# Main.net
KiCad netlist of a schematic drawn in Altium Designer
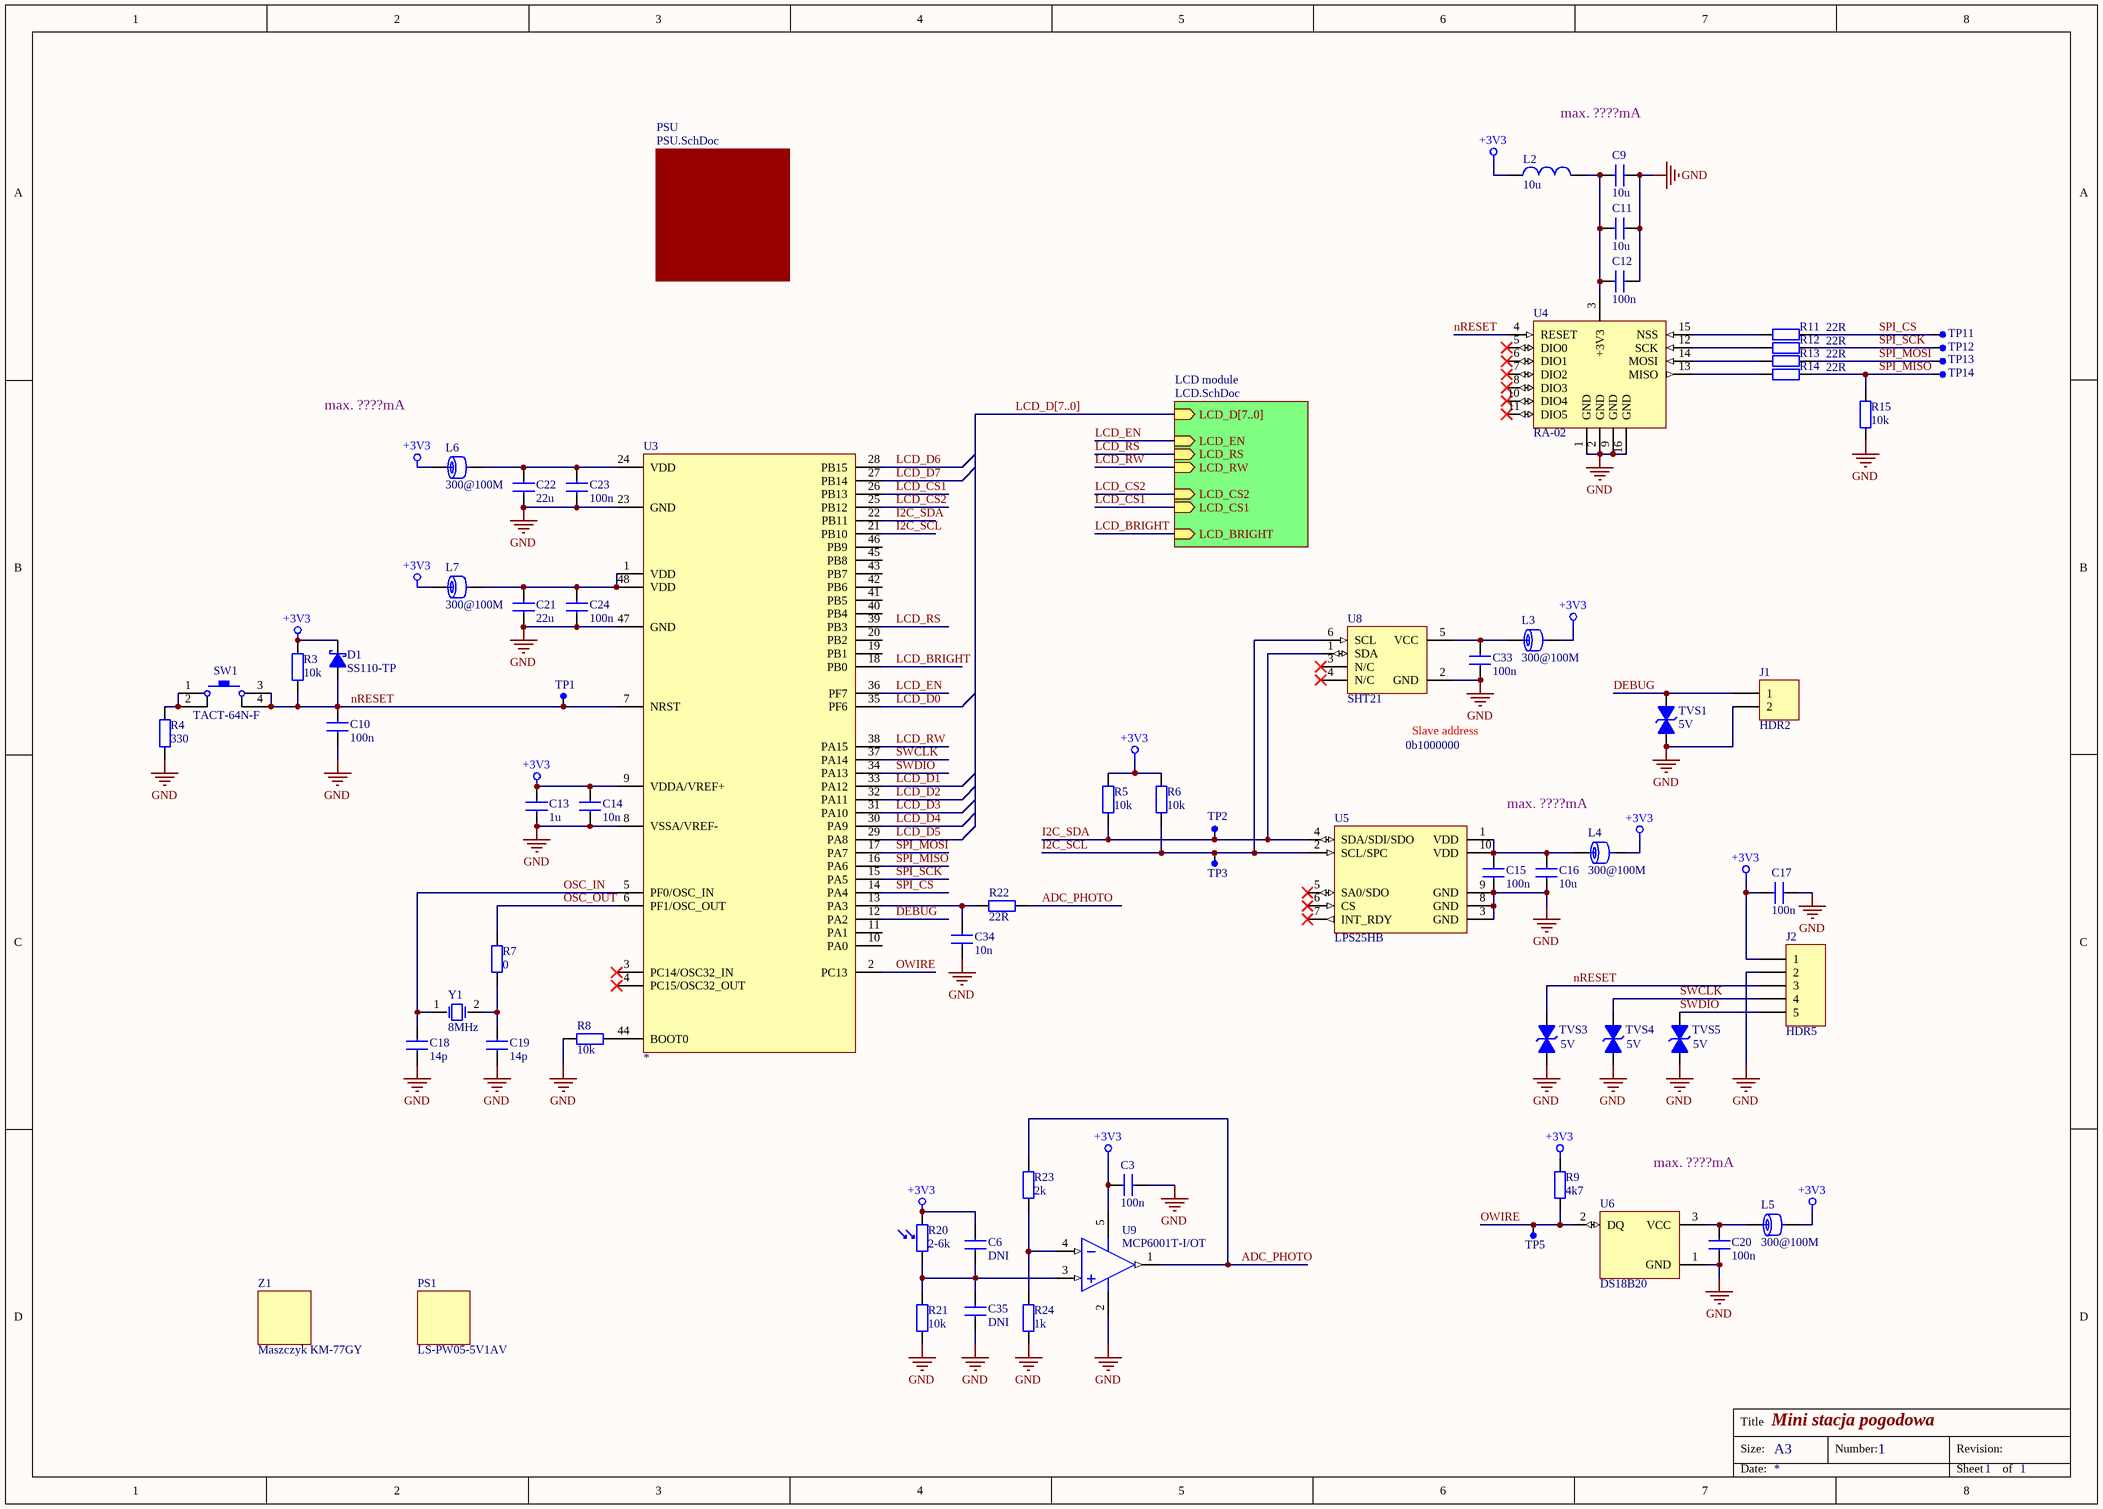
[diagram p0: Main.SchDoc]

(export (version "E")
  (design (tool "Eeschema 10.0.6"))
  (components
    (comp (ref "C3")
      (value "100n")
      (footprint "C_0805")
      (description "Capacitor")
      (libsource (lib "passive") (part "Capacitor"))
    )
    (comp (ref "C6")
      (value "DNI")
      (footprint "C_0805")
      (description "Capacitor")
      (libsource (lib "passive") (part "Capacitor"))
    )
    (comp (ref "C9")
      (value "10u")
      (footprint "C_0805")
      (description "Capacitor")
      (libsource (lib "passive") (part "Capacitor"))
    )
    (comp (ref "C10")
      (value "100n")
      (footprint "C_0805")
      (description "Capacitor")
      (libsource (lib "passive") (part "Capacitor"))
    )
    (comp (ref "C11")
      (value "10u")
      (footprint "C_0805")
      (description "Capacitor")
      (libsource (lib "passive") (part "Capacitor"))
    )
    (comp (ref "C12")
      (value "100n")
      (footprint "C_0805")
      (description "Capacitor")
      (libsource (lib "passive") (part "Capacitor"))
    )
    (comp (ref "C13")
      (value "1u")
      (footprint "C_0805")
      (description "Capacitor")
      (libsource (lib "passive") (part "Capacitor"))
    )
    (comp (ref "C14")
      (value "10n")
      (footprint "C_0805")
      (description "Capacitor")
      (libsource (lib "passive") (part "Capacitor"))
    )
    (comp (ref "C15")
      (value "100n")
      (footprint "C_0805")
      (description "Capacitor")
      (libsource (lib "passive") (part "Capacitor"))
    )
    (comp (ref "C16")
      (value "10u")
      (footprint "C_0805")
      (description "Capacitor")
      (libsource (lib "passive") (part "Capacitor"))
    )
    (comp (ref "C17")
      (value "100n")
      (footprint "C_0805")
      (description "Capacitor")
      (libsource (lib "passive") (part "Capacitor"))
    )
    (comp (ref "C18")
      (value "14p")
      (footprint "C_0805")
      (description "Capacitor")
      (libsource (lib "passive") (part "Capacitor"))
    )
    (comp (ref "C19")
      (value "14p")
      (footprint "C_0805")
      (description "Capacitor")
      (libsource (lib "passive") (part "Capacitor"))
    )
    (comp (ref "C20")
      (value "100n")
      (footprint "C_0805")
      (description "Capacitor")
      (libsource (lib "passive") (part "Capacitor"))
    )
    (comp (ref "C21")
      (value "22u")
      (footprint "C_0805")
      (description "Capacitor")
      (libsource (lib "passive") (part "Capacitor"))
    )
    (comp (ref "C22")
      (value "22u")
      (footprint "C_0805")
      (description "Capacitor")
      (libsource (lib "passive") (part "Capacitor"))
    )
    (comp (ref "C23")
      (value "100n")
      (footprint "C_0805")
      (description "Capacitor")
      (libsource (lib "passive") (part "Capacitor"))
    )
    (comp (ref "C24")
      (value "100n")
      (footprint "C_0805")
      (description "Capacitor")
      (libsource (lib "passive") (part "Capacitor"))
    )
    (comp (ref "C33")
      (value "100n")
      (footprint "C_0805")
      (description "Capacitor")
      (libsource (lib "passive") (part "Capacitor"))
    )
    (comp (ref "C34")
      (value "10n")
      (footprint "C_0805")
      (description "Capacitor")
      (libsource (lib "passive") (part "Capacitor"))
    )
    (comp (ref "C35")
      (value "DNI")
      (footprint "C_0805")
      (description "Capacitor")
      (libsource (lib "passive") (part "Capacitor"))
    )
    (comp (ref "D1")
      (value "SS110-TP")
      (footprint "D_1206")
      (description "Schottky Diode")
      (libsource (lib "passive") (part "Diode Schottky"))
    )
    (comp (ref "J1")
      (value "HDR2")
      (footprint "header 2.54mm 2pin")
      (description "Header, 2-Pin")
      (fields (field (name "Comment") "Header 2"))
      (libsource (lib "mechanical") (part "Header 2"))
    )
    (comp (ref "J2")
      (value "HDR5")
      (footprint "header 2.54mm 5pin")
      (description "Header, 5-Pin")
      (fields (field (name "Comment") "Header 5"))
      (libsource (lib "mechanical") (part "Header 5"))
    )
    (comp (ref "L2")
      (value "10u")
      (footprint "L_0805")
      (description "Inductor")
      (libsource (lib "passive") (part "Inductor"))
    )
    (comp (ref "L3")
      (value "300@100M")
      (footprint "L_0805")
      (description "Ferrite Bead")
      (fields (field (name "Comment") "742792031"))
      (libsource (lib "passive") (part "FB"))
    )
    (comp (ref "L4")
      (value "300@100M")
      (footprint "L_0805")
      (description "Ferrite Bead")
      (fields (field (name "Comment") "742792031"))
      (libsource (lib "passive") (part "FB"))
    )
    (comp (ref "L5")
      (value "300@100M")
      (footprint "L_0805")
      (description "Ferrite Bead")
      (fields (field (name "Comment") "742792031"))
      (libsource (lib "passive") (part "FB"))
    )
    (comp (ref "L6")
      (value "300@100M")
      (footprint "L_0805")
      (description "Ferrite Bead")
      (fields (field (name "Comment") "742792031"))
      (libsource (lib "passive") (part "FB"))
    )
    (comp (ref "L7")
      (value "300@100M")
      (footprint "L_0805")
      (description "Ferrite Bead")
      (fields (field (name "Comment") "742792031"))
      (libsource (lib "passive") (part "FB"))
    )
    (comp (ref "PS1")
      (value "LS-PW05-5V1AV")
      (description "5VDC; 1A; EU; 82,7%")
      (libsource (lib "mechanical") (part "LS-PW05-5V1AV"))
    )
    (comp (ref "R3")
      (value "10k")
      (footprint "R_0805")
      (description "Resistor")
      (libsource (lib "passive") (part "Resistor"))
    )
    (comp (ref "R4")
      (value "330")
      (footprint "R_0805")
      (description "Resistor")
      (libsource (lib "passive") (part "Resistor"))
    )
    (comp (ref "R5")
      (value "10k")
      (footprint "R_1206")
      (description "Resistor")
      (libsource (lib "passive") (part "Resistor"))
    )
    (comp (ref "R6")
      (value "10k")
      (footprint "R_1206")
      (description "Resistor")
      (libsource (lib "passive") (part "Resistor"))
    )
    (comp (ref "R7")
      (value "0")
      (footprint "R_0805")
      (description "Resistor")
      (libsource (lib "passive") (part "Resistor"))
    )
    (comp (ref "R8")
      (value "10k")
      (footprint "R_1206")
      (description "Resistor")
      (libsource (lib "") (part "Resistor_1"))
    )
    (comp (ref "R9")
      (value "4k7")
      (footprint "R_1206")
      (description "Resistor")
      (libsource (lib "boxer_pas") (part "Resistor"))
    )
    (comp (ref "R11")
      (value "22R")
      (footprint "R_0805")
      (description "Resistor")
      (libsource (lib "") (part "Resistor_1"))
    )
    (comp (ref "R12")
      (value "22R")
      (footprint "R_0805")
      (description "Resistor")
      (libsource (lib "") (part "Resistor_1"))
    )
    (comp (ref "R13")
      (value "22R")
      (footprint "R_0805")
      (description "Resistor")
      (libsource (lib "") (part "Resistor_1"))
    )
    (comp (ref "R14")
      (value "22R")
      (footprint "R_0805")
      (description "Resistor")
      (libsource (lib "") (part "Resistor_1"))
    )
    (comp (ref "R15")
      (value "10k")
      (footprint "R_1206")
      (description "Resistor")
      (libsource (lib "passive") (part "Resistor"))
    )
    (comp (ref "R20")
      (value "2-6k")
      (footprint "Photoresistor")
      (description "Photo Resistor")
      (fields (field (name "Comment") "PGM5506-MP"))
      (libsource (lib "passive") (part "Resistor Photo"))
    )
    (comp (ref "R21")
      (value "10k")
      (footprint "R_1206")
      (description "Resistor")
      (libsource (lib "passive") (part "Resistor"))
    )
    (comp (ref "R22")
      (value "22R")
      (footprint "R_0805")
      (description "Resistor")
      (libsource (lib "") (part "Resistor_1"))
    )
    (comp (ref "R23")
      (value "2k")
      (footprint "R_1206")
      (description "Resistor")
      (libsource (lib "passive") (part "Resistor"))
    )
    (comp (ref "R24")
      (value "1k")
      (footprint "R_1206")
      (description "Resistor")
      (libsource (lib "passive") (part "Resistor"))
    )
    (comp (ref "SW1")
      (value "TACT-64N-F")
      (footprint "SPST_NO_1301")
      (description "Switch 4 Pins")
      (fields (field (name "Comment") "Switch-PB 4 Pins"))
      (libsource (lib "mechanical") (part "Switch-PB 4 Pins"))
    )
    (comp (ref "TP1")
      (value "TEST PAD")
      (footprint "PIN")
      (description "PAD 1.5mm")
      (libsource (lib "boxer_mechanical") (part "TEST_PAD"))
    )
    (comp (ref "TP2")
      (value "TEST PAD")
      (footprint "PIN")
      (libsource (lib "boxer_mechanical") (part "TEST_PAD"))
    )
    (comp (ref "TP3")
      (value "TEST PAD")
      (footprint "PIN")
      (libsource (lib "boxer_mechanical") (part "TEST_PAD"))
    )
    (comp (ref "TP5")
      (value "TEST PAD")
      (footprint "PIN")
      (libsource (lib "boxer_mechanical") (part "TEST_PAD"))
    )
    (comp (ref "TP11")
      (value "TEST PAD")
      (footprint "PIN")
      (description "PAD 1.5mm")
      (libsource (lib "mechanical") (part "TEST_PAD"))
    )
    (comp (ref "TP12")
      (value "TEST PAD")
      (footprint "PIN")
      (description "PAD 1.5mm")
      (libsource (lib "mechanical") (part "TEST_PAD"))
    )
    (comp (ref "TP13")
      (value "TEST PAD")
      (footprint "PIN")
      (description "PAD 1.5mm")
      (libsource (lib "mechanical") (part "TEST_PAD"))
    )
    (comp (ref "TP14")
      (value "TEST PAD")
      (footprint "PIN")
      (description "PAD 1.5mm")
      (libsource (lib "mechanical") (part "TEST_PAD"))
    )
    (comp (ref "TVS1")
      (value "5V")
      (footprint "D_1206")
      (description "Transil")
      (fields (field (name "Comment") "SMAJ5.0ALFCT-ND"))
      (libsource (lib "passive") (part "Transil"))
    )
    (comp (ref "TVS3")
      (value "5V")
      (footprint "D_SMA")
      (description "Transil")
      (fields (field (name "Comment") "SMAJ5.0ALFCT-ND"))
      (libsource (lib "boxer_pas") (part "Transil"))
    )
    (comp (ref "TVS4")
      (value "5V")
      (footprint "D_SMA")
      (description "Transil")
      (fields (field (name "Comment") "SMAJ5.0ALFCT-ND"))
      (libsource (lib "boxer_pas") (part "Transil"))
    )
    (comp (ref "TVS5")
      (value "5V")
      (footprint "D_SMA")
      (description "Transil")
      (fields (field (name "Comment") "SMAJ5.0ALFCT-ND"))
      (libsource (lib "boxer_pas") (part "Transil"))
    )
    (comp (ref "U3")
      (value "STM32F030C6T6")
      (footprint "LQFP-48")
      (description "Microcontroler ARM; Flash: 32kB; 48MHz; SRAM: 4kB; LQFP48")
      (fields (field (name "ALTIUM_VALUE") "*"))
      (libsource (lib "digital") (part "STM32F030C6T6"))
    )
    (comp (ref "U4")
      (value "RA-02")
      (footprint "RA-02")
      (description "LoRa RA-02 SX1278 433MHz")
      (libsource (lib "digital") (part "RA-02 SX1278"))
    )
    (comp (ref "U5")
      (value "LPS25HB")
      (footprint "digital:LPS25HB")
      (description "MEMS pressure sensor: 260-1260 hPa absolute digital output barometer, HCLGA10, STM, RoHS")
      (libsource (lib "digital") (part "LPS25HB"))
    )
    (comp (ref "U6")
      (value "DS18B20")
      (footprint "TO-92")
      (description "DS18B20  Programmable Resolution  1-Wire Digital Thermometer")
      (libsource (lib "digital") (part "DS18B20"))
    )
    (comp (ref "U8")
      (value "SHT21")
      (footprint "DFN6")
      (description "Humidity and Temperature Sensor IC")
      (libsource (lib "digital") (part "SHT21"))
    )
    (comp (ref "U9")
      (value "MCP6001T-I/OT")
      (footprint "SOT23-5")
      (description "Rail to Rail Operational Amplifier")
      (fields (field (name "Comment") "MCP6001T"))
      (libsource (lib "digital") (part "MCP6001T"))
    )
    (comp (ref "Y1")
      (value "8MHz")
      (footprint "CFPX_217")
      (description "Crystal Oscillator")
      (fields (field (name "Comment") "7A-8.000MAAE-T"))
      (libsource (lib "passive") (part "XTAL"))
    )
    (comp (ref "Z1")
      (value "Maszczyk KM-77GY")
      (footprint "KM-77GY")
      (description "X:80mm; Y:120mm; Z:31mm; ABS; gray")
      (libsource (lib "mechanical") (part "KM-77GY"))
    )
  )
  (nets
    (net (code "1") (name "+3V3") (class "Default")
      (node (ref "C13") (pin "2") (pinfunction "2_2") (pintype "passive"))
      (node (ref "C14") (pin "2") (pinfunction "2_2") (pintype "passive"))
      (node (ref "C17") (pin "2") (pinfunction "2_2") (pintype "passive"))
      (node (ref "C3") (pin "2") (pinfunction "2_2") (pintype "passive"))
      (node (ref "C6") (pin "1") (pinfunction "1_1") (pintype "passive"))
      (node (ref "D1") (pin "2") (pinfunction "K_2") (pintype "passive"))
      (node (ref "J2") (pin "1") (pinfunction "1_1") (pintype "passive"))
      (node (ref "L2") (pin "1") (pinfunction "1_1") (pintype "passive"))
      (node (ref "L3") (pin "2") (pinfunction "2_2") (pintype "passive"))
      (node (ref "L4") (pin "2") (pinfunction "2_2") (pintype "passive"))
      (node (ref "L5") (pin "2") (pinfunction "2_2") (pintype "passive"))
      (node (ref "L6") (pin "1") (pinfunction "1_1") (pintype "passive"))
      (node (ref "L7") (pin "1") (pinfunction "1_1") (pintype "passive"))
      (node (ref "R20") (pin "1") (pinfunction "1_1") (pintype "passive"))
      (node (ref "R3") (pin "2") (pinfunction "2_2") (pintype "passive"))
      (node (ref "R5") (pin "2") (pinfunction "2_2") (pintype "passive"))
      (node (ref "R6") (pin "2") (pinfunction "2_2") (pintype "passive"))
      (node (ref "R9") (pin "2") (pinfunction "2_2") (pintype "passive"))
      (node (ref "U3") (pin "9") (pinfunction "VDDA/VREF+_9") (pintype "passive"))
      (node (ref "U9") (pin "5") (pinfunction "VCC+_5") (pintype "power_in"))
    )
    (net (code "2") (name "/ADC_PHOTO") (class "Default")
      (node (ref "R22") (pin "1") (pinfunction "1_1") (pintype "passive"))
      (node (ref "R23") (pin "2") (pinfunction "2_2") (pintype "passive"))
      (node (ref "U9") (pin "1") (pinfunction "OUT_1") (pintype "output"))
    )
    (net (code "3") (name "/DEBUG") (class "Default")
      (node (ref "J1") (pin "1") (pinfunction "1_1") (pintype "passive"))
      (node (ref "TVS1") (pin "2") (pinfunction "K_2") (pintype "passive"))
      (node (ref "U3") (pin "12") (pinfunction "PA2_12") (pintype "passive"))
    )
    (net (code "4") (name "/I2C_SCL") (class "Default")
      (node (ref "R6") (pin "1") (pinfunction "1_1") (pintype "passive"))
      (node (ref "TP3") (pin "1") (pinfunction "1_1") (pintype "passive"))
      (node (ref "U3") (pin "21") (pinfunction "PB10_21") (pintype "passive"))
      (node (ref "U5") (pin "2") (pinfunction "SCL/SPC_2") (pintype "input"))
      (node (ref "U8") (pin "6") (pinfunction "SCL_6") (pintype "input"))
    )
    (net (code "5") (name "/I2C_SDA") (class "Default")
      (node (ref "R5") (pin "1") (pinfunction "1_1") (pintype "passive"))
      (node (ref "TP2") (pin "1") (pinfunction "1_1") (pintype "passive"))
      (node (ref "U3") (pin "22") (pinfunction "PB11_22") (pintype "passive"))
      (node (ref "U5") (pin "4") (pinfunction "SDA/SDI/SDO_4") (pintype "bidirectional"))
      (node (ref "U8") (pin "1") (pinfunction "SDA_1") (pintype "bidirectional"))
    )
    (net (code "6") (name "/LCD_BRIGHT") (class "Default")
      (node (ref "U3") (pin "18") (pinfunction "PB0_18") (pintype "passive"))
    )
    (net (code "7") (name "/LCD_CS1") (class "Default")
      (node (ref "U3") (pin "26") (pinfunction "PB13_26") (pintype "passive"))
    )
    (net (code "8") (name "/LCD_CS2") (class "Default")
      (node (ref "U3") (pin "25") (pinfunction "PB12_25") (pintype "passive"))
    )
    (net (code "9") (name "/LCD_D0") (class "Default")
      (node (ref "U3") (pin "35") (pinfunction "PF6_35") (pintype "passive"))
    )
    (net (code "10") (name "/LCD_D1") (class "Default")
      (node (ref "U3") (pin "33") (pinfunction "PA12_33") (pintype "passive"))
    )
    (net (code "11") (name "/LCD_D2") (class "Default")
      (node (ref "U3") (pin "32") (pinfunction "PA11_32") (pintype "passive"))
    )
    (net (code "12") (name "/LCD_D3") (class "Default")
      (node (ref "U3") (pin "31") (pinfunction "PA10_31") (pintype "passive"))
    )
    (net (code "13") (name "/LCD_D4") (class "Default")
      (node (ref "U3") (pin "30") (pinfunction "PA9_30") (pintype "passive"))
    )
    (net (code "14") (name "/LCD_D5") (class "Default")
      (node (ref "U3") (pin "29") (pinfunction "PA8_29") (pintype "passive"))
    )
    (net (code "15") (name "/LCD_D6") (class "Default")
      (node (ref "U3") (pin "28") (pinfunction "PB15_28") (pintype "passive"))
    )
    (net (code "16") (name "/LCD_D7") (class "Default")
      (node (ref "U3") (pin "27") (pinfunction "PB14_27") (pintype "passive"))
    )
    (net (code "18") (name "/LCD_EN") (class "Default")
      (node (ref "U3") (pin "36") (pinfunction "PF7_36") (pintype "passive"))
    )
    (net (code "19") (name "/LCD_RS") (class "Default")
      (node (ref "U3") (pin "39") (pinfunction "PB3_39") (pintype "passive"))
    )
    (net (code "20") (name "/LCD_RW") (class "Default")
      (node (ref "U3") (pin "38") (pinfunction "PA15_38") (pintype "passive"))
    )
    (net (code "21") (name "/OSC_IN") (class "Default")
      (node (ref "C18") (pin "2") (pinfunction "2_2") (pintype "passive"))
      (node (ref "U3") (pin "5") (pinfunction "PF0/OSC_IN_5") (pintype "passive"))
      (node (ref "Y1") (pin "1") (pinfunction "OSC1_1") (pintype "passive"))
    )
    (net (code "22") (name "/OSC_OUT") (class "Default")
      (node (ref "R7") (pin "2") (pinfunction "2_2") (pintype "passive"))
      (node (ref "U3") (pin "6") (pinfunction "PF1/OSC_OUT_6") (pintype "passive"))
    )
    (net (code "23") (name "/OWIRE") (class "Default")
      (node (ref "R9") (pin "1") (pinfunction "1_1") (pintype "passive"))
      (node (ref "TP5") (pin "1") (pinfunction "1_1") (pintype "passive"))
      (node (ref "U3") (pin "2") (pinfunction "PC13_2") (pintype "passive"))
      (node (ref "U6") (pin "2") (pinfunction "DQ_2") (pintype "bidirectional"))
    )
    (net (code "24") (name "/SPI_CS") (class "Default")
      (node (ref "R11") (pin "1") (pinfunction "1_1") (pintype "passive"))
      (node (ref "TP11") (pin "1") (pinfunction "1_1") (pintype "passive"))
      (node (ref "U3") (pin "14") (pinfunction "PA4_14") (pintype "passive"))
    )
    (net (code "25") (name "/SPI_MISO") (class "Default")
      (node (ref "R14") (pin "1") (pinfunction "1_1") (pintype "passive"))
      (node (ref "R15") (pin "2") (pinfunction "2_2") (pintype "passive"))
      (node (ref "TP14") (pin "1") (pinfunction "1_1") (pintype "passive"))
      (node (ref "U3") (pin "16") (pinfunction "PA6_16") (pintype "passive"))
    )
    (net (code "26") (name "/SPI_MOSI") (class "Default")
      (node (ref "R13") (pin "1") (pinfunction "1_1") (pintype "passive"))
      (node (ref "TP13") (pin "1") (pinfunction "1_1") (pintype "passive"))
      (node (ref "U3") (pin "17") (pinfunction "PA7_17") (pintype "passive"))
    )
    (net (code "27") (name "/SPI_SCK") (class "Default")
      (node (ref "R12") (pin "1") (pinfunction "1_1") (pintype "passive"))
      (node (ref "TP12") (pin "1") (pinfunction "1_1") (pintype "passive"))
      (node (ref "U3") (pin "15") (pinfunction "PA5_15") (pintype "passive"))
    )
    (net (code "28") (name "/SWCLK") (class "Default")
      (node (ref "J2") (pin "4") (pinfunction "4_4") (pintype "passive"))
      (node (ref "TVS4") (pin "2") (pinfunction "K_2") (pintype "passive"))
      (node (ref "U3") (pin "37") (pinfunction "PA14_37") (pintype "passive"))
    )
    (net (code "29") (name "/SWDIO") (class "Default")
      (node (ref "J2") (pin "5") (pinfunction "5_5") (pintype "passive"))
      (node (ref "TVS5") (pin "2") (pinfunction "K_2") (pintype "passive"))
      (node (ref "U3") (pin "34") (pinfunction "PA13_34") (pintype "passive"))
    )
    (net (code "30") (name "/nRESET") (class "Default")
      (node (ref "C10") (pin "2") (pinfunction "2_2") (pintype "passive"))
      (node (ref "D1") (pin "1") (pinfunction "A_1") (pintype "passive"))
      (node (ref "J2") (pin "3") (pinfunction "3_3") (pintype "passive"))
      (node (ref "R3") (pin "1") (pinfunction "1_1") (pintype "passive"))
      (node (ref "SW1") (pin "3") (pinfunction "3_3") (pintype "passive"))
      (node (ref "SW1") (pin "4") (pinfunction "4_4") (pintype "passive"))
      (node (ref "TP1") (pin "1") (pinfunction "1_1") (pintype "passive"))
      (node (ref "TVS3") (pin "2") (pinfunction "K_2") (pintype "passive"))
      (node (ref "U3") (pin "7") (pinfunction "NRST_7") (pintype "passive"))
      (node (ref "U4") (pin "4") (pinfunction "RESET_4") (pintype "input"))
    )
    (net (code "31") (name "GND") (class "Default")
      (node (ref "C10") (pin "1") (pinfunction "1_1") (pintype "passive"))
      (node (ref "C11") (pin "1") (pinfunction "1_1") (pintype "passive"))
      (node (ref "C12") (pin "1") (pinfunction "1_1") (pintype "passive"))
      (node (ref "C13") (pin "1") (pinfunction "1_1") (pintype "passive"))
      (node (ref "C14") (pin "1") (pinfunction "1_1") (pintype "passive"))
      (node (ref "C15") (pin "1") (pinfunction "1_1") (pintype "passive"))
      (node (ref "C16") (pin "1") (pinfunction "1_1") (pintype "passive"))
      (node (ref "C17") (pin "1") (pinfunction "1_1") (pintype "passive"))
      (node (ref "C18") (pin "1") (pinfunction "1_1") (pintype "passive"))
      (node (ref "C19") (pin "1") (pinfunction "1_1") (pintype "passive"))
      (node (ref "C20") (pin "1") (pinfunction "1_1") (pintype "passive"))
      (node (ref "C21") (pin "2") (pinfunction "2_2") (pintype "passive"))
      (node (ref "C22") (pin "2") (pinfunction "2_2") (pintype "passive"))
      (node (ref "C23") (pin "2") (pinfunction "2_2") (pintype "passive"))
      (node (ref "C24") (pin "2") (pinfunction "2_2") (pintype "passive"))
      (node (ref "C3") (pin "1") (pinfunction "1_1") (pintype "passive"))
      (node (ref "C33") (pin "1") (pinfunction "1_1") (pintype "passive"))
      (node (ref "C34") (pin "1") (pinfunction "1_1") (pintype "passive"))
      (node (ref "C35") (pin "2") (pinfunction "2_2") (pintype "passive"))
      (node (ref "C9") (pin "1") (pinfunction "1_1") (pintype "passive"))
      (node (ref "J1") (pin "2") (pinfunction "2_2") (pintype "passive"))
      (node (ref "J2") (pin "2") (pinfunction "2_2") (pintype "passive"))
      (node (ref "R15") (pin "1") (pinfunction "1_1") (pintype "passive"))
      (node (ref "R21") (pin "1") (pinfunction "1_1") (pintype "passive"))
      (node (ref "R24") (pin "1") (pinfunction "1_1") (pintype "passive"))
      (node (ref "R4") (pin "1") (pinfunction "1_1") (pintype "passive"))
      (node (ref "R8") (pin "2") (pinfunction "2_2") (pintype "passive"))
      (node (ref "TVS1") (pin "1") (pinfunction "A_1") (pintype "passive"))
      (node (ref "TVS3") (pin "1") (pinfunction "A_1") (pintype "passive"))
      (node (ref "TVS4") (pin "1") (pinfunction "A_1") (pintype "passive"))
      (node (ref "TVS5") (pin "1") (pinfunction "A_1") (pintype "passive"))
      (node (ref "U3") (pin "23") (pinfunction "GND_23") (pintype "power_in"))
      (node (ref "U3") (pin "47") (pinfunction "GND_47") (pintype "power_in"))
      (node (ref "U3") (pin "8") (pinfunction "VSSA/VREF-_8") (pintype "passive"))
      (node (ref "U4") (pin "1") (pinfunction "GND_1") (pintype "power_in"))
      (node (ref "U4") (pin "16") (pinfunction "GND_16") (pintype "power_in"))
      (node (ref "U4") (pin "2") (pinfunction "GND_2") (pintype "power_in"))
      (node (ref "U4") (pin "9") (pinfunction "GND_9") (pintype "power_in"))
      (node (ref "U5") (pin "3") (pinfunction "GND_3") (pintype "power_in"))
      (node (ref "U5") (pin "8") (pinfunction "GND_8") (pintype "power_in"))
      (node (ref "U5") (pin "9") (pinfunction "GND_9") (pintype "power_in"))
      (node (ref "U6") (pin "1") (pinfunction "GND_1") (pintype "power_in"))
      (node (ref "U8") (pin "2") (pinfunction "GND_2") (pintype "power_in"))
      (node (ref "U9") (pin "2") (pinfunction "VCC-_2") (pintype "power_in"))
    )
    (net (code "32") (name "Net-(C15-Pad2)") (class "Default")
      (node (ref "C15") (pin "2") (pinfunction "2_2") (pintype "passive"))
      (node (ref "C16") (pin "2") (pinfunction "2_2") (pintype "passive"))
      (node (ref "L4") (pin "1") (pinfunction "1_1") (pintype "passive"))
      (node (ref "U5") (pin "1") (pinfunction "VDD_1") (pintype "power_in"))
      (node (ref "U5") (pin "10") (pinfunction "VDD_10") (pintype "power_in"))
    )
    (net (code "33") (name "Net-(C21-Pad1)") (class "Default")
      (node (ref "C21") (pin "1") (pinfunction "1_1") (pintype "passive"))
      (node (ref "C24") (pin "1") (pinfunction "1_1") (pintype "passive"))
      (node (ref "L7") (pin "2") (pinfunction "2_2") (pintype "passive"))
      (node (ref "U3") (pin "1") (pinfunction "VDD_1") (pintype "power_in"))
      (node (ref "U3") (pin "48") (pinfunction "VDD_48") (pintype "power_in"))
    )
    (net (code "34") (name "Net-(C22-Pad1)") (class "Default")
      (node (ref "C22") (pin "1") (pinfunction "1_1") (pintype "passive"))
      (node (ref "C23") (pin "1") (pinfunction "1_1") (pintype "passive"))
      (node (ref "L6") (pin "2") (pinfunction "2_2") (pintype "passive"))
      (node (ref "U3") (pin "24") (pinfunction "VDD_24") (pintype "power_in"))
    )
    (net (code "35") (name "Net-(R4-Pad2)") (class "Default")
      (node (ref "R4") (pin "2") (pinfunction "2_2") (pintype "passive"))
      (node (ref "SW1") (pin "1") (pinfunction "1_1") (pintype "passive"))
      (node (ref "SW1") (pin "2") (pinfunction "2_2") (pintype "passive"))
    )
    (net (code "36") (name "Net-(U3-BOOT0)") (class "Default")
      (node (ref "R8") (pin "1") (pinfunction "1_1") (pintype "passive"))
      (node (ref "U3") (pin "44") (pinfunction "BOOT0_44") (pintype "passive"))
    )
    (net (code "37") (name "Net-(U3-PA3)") (class "Default")
      (node (ref "C34") (pin "2") (pinfunction "2_2") (pintype "passive"))
      (node (ref "R22") (pin "2") (pinfunction "2_2") (pintype "passive"))
      (node (ref "U3") (pin "13") (pinfunction "PA3_13") (pintype "passive"))
    )
    (net (code "38") (name "Net-(U4-+3V3)") (class "Default")
      (node (ref "C11") (pin "2") (pinfunction "2_2") (pintype "passive"))
      (node (ref "C12") (pin "2") (pinfunction "2_2") (pintype "passive"))
      (node (ref "C9") (pin "2") (pinfunction "2_2") (pintype "passive"))
      (node (ref "L2") (pin "2") (pinfunction "2_2") (pintype "passive"))
      (node (ref "U4") (pin "3") (pinfunction "+3V3_3") (pintype "power_in"))
    )
    (net (code "39") (name "Net-(U4-MISO)") (class "Default")
      (node (ref "R14") (pin "2") (pinfunction "2_2") (pintype "passive"))
      (node (ref "U4") (pin "13") (pinfunction "MISO_13") (pintype "output"))
    )
    (net (code "40") (name "Net-(U4-MOSI)") (class "Default")
      (node (ref "R13") (pin "2") (pinfunction "2_2") (pintype "passive"))
      (node (ref "U4") (pin "14") (pinfunction "MOSI_14") (pintype "input"))
    )
    (net (code "41") (name "Net-(U4-NSS)") (class "Default")
      (node (ref "R11") (pin "2") (pinfunction "2_2") (pintype "passive"))
      (node (ref "U4") (pin "15") (pinfunction "NSS_15") (pintype "input"))
    )
    (net (code "42") (name "Net-(U4-SCK)") (class "Default")
      (node (ref "R12") (pin "2") (pinfunction "2_2") (pintype "passive"))
      (node (ref "U4") (pin "12") (pinfunction "SCK_12") (pintype "input"))
    )
    (net (code "43") (name "Net-(U6-VCC)") (class "Default")
      (node (ref "C20") (pin "2") (pinfunction "2_2") (pintype "passive"))
      (node (ref "L5") (pin "1") (pinfunction "1_1") (pintype "passive"))
      (node (ref "U6") (pin "3") (pinfunction "VCC_3") (pintype "power_in"))
    )
    (net (code "44") (name "Net-(U8-VCC)") (class "Default")
      (node (ref "C33") (pin "2") (pinfunction "2_2") (pintype "passive"))
      (node (ref "L3") (pin "1") (pinfunction "1_1") (pintype "passive"))
      (node (ref "U8") (pin "5") (pinfunction "VCC_5") (pintype "power_in"))
    )
    (net (code "45") (name "Net-(U9-IN+)") (class "Default")
      (node (ref "C35") (pin "1") (pinfunction "1_1") (pintype "passive"))
      (node (ref "C6") (pin "2") (pinfunction "2_2") (pintype "passive"))
      (node (ref "R20") (pin "2") (pinfunction "2_2") (pintype "passive"))
      (node (ref "R21") (pin "2") (pinfunction "2_2") (pintype "passive"))
      (node (ref "U9") (pin "3") (pinfunction "IN+_3") (pintype "input"))
    )
    (net (code "46") (name "Net-(U9-IN-)") (class "Default")
      (node (ref "R23") (pin "1") (pinfunction "1_1") (pintype "passive"))
      (node (ref "R24") (pin "2") (pinfunction "2_2") (pintype "passive"))
      (node (ref "U9") (pin "4") (pinfunction "IN-_4") (pintype "input"))
    )
    (net (code "47") (name "Net-(Y1-OSC2)") (class "Default")
      (node (ref "C19") (pin "2") (pinfunction "2_2") (pintype "passive"))
      (node (ref "R7") (pin "1") (pinfunction "1_1") (pintype "passive"))
      (node (ref "Y1") (pin "2") (pinfunction "OSC2_2") (pintype "passive"))
    )
    (net (code "48") (name "unconnected-(U3-PA0-Pad10)") (class "Default")
      (node (ref "U3") (pin "10") (pinfunction "PA0_10") (pintype "passive"))
    )
    (net (code "49") (name "unconnected-(U3-PA1-Pad11)") (class "Default")
      (node (ref "U3") (pin "11") (pinfunction "PA1_11") (pintype "passive"))
    )
    (net (code "50") (name "unconnected-(U3-PB1-Pad19)") (class "Default")
      (node (ref "U3") (pin "19") (pinfunction "PB1_19") (pintype "passive"))
    )
    (net (code "51") (name "unconnected-(U3-PB2-Pad20)") (class "Default")
      (node (ref "U3") (pin "20") (pinfunction "PB2_20") (pintype "passive"))
    )
    (net (code "52") (name "unconnected-(U3-PB4-Pad40)") (class "Default")
      (node (ref "U3") (pin "40") (pinfunction "PB4_40") (pintype "passive"))
    )
    (net (code "53") (name "unconnected-(U3-PB5-Pad41)") (class "Default")
      (node (ref "U3") (pin "41") (pinfunction "PB5_41") (pintype "passive"))
    )
    (net (code "54") (name "unconnected-(U3-PB6-Pad42)") (class "Default")
      (node (ref "U3") (pin "42") (pinfunction "PB6_42") (pintype "passive"))
    )
    (net (code "55") (name "unconnected-(U3-PB7-Pad43)") (class "Default")
      (node (ref "U3") (pin "43") (pinfunction "PB7_43") (pintype "passive"))
    )
    (net (code "56") (name "unconnected-(U3-PB8-Pad45)") (class "Default")
      (node (ref "U3") (pin "45") (pinfunction "PB8_45") (pintype "passive"))
    )
    (net (code "57") (name "unconnected-(U3-PB9-Pad46)") (class "Default")
      (node (ref "U3") (pin "46") (pinfunction "PB9_46") (pintype "passive"))
    )
    (net (code "58") (name "unconnected-(U3-PC14{slash}OSC32_IN-Pad3)") (class "Default")
      (node (ref "U3") (pin "3") (pinfunction "PC14/OSC32_IN_3") (pintype "passive+no_connect"))
    )
    (net (code "59") (name "unconnected-(U3-PC15{slash}OSC32_OUT-Pad4)") (class "Default")
      (node (ref "U3") (pin "4") (pinfunction "PC15/OSC32_OUT_4") (pintype "passive+no_connect"))
    )
    (net (code "60") (name "unconnected-(U4-DIO0-Pad5)") (class "Default")
      (node (ref "U4") (pin "5") (pinfunction "DIO0_5") (pintype "bidirectional+no_connect"))
    )
    (net (code "61") (name "unconnected-(U4-DIO1-Pad6)") (class "Default")
      (node (ref "U4") (pin "6") (pinfunction "DIO1_6") (pintype "bidirectional+no_connect"))
    )
    (net (code "62") (name "unconnected-(U4-DIO2-Pad7)") (class "Default")
      (node (ref "U4") (pin "7") (pinfunction "DIO2_7") (pintype "bidirectional+no_connect"))
    )
    (net (code "63") (name "unconnected-(U4-DIO3-Pad8)") (class "Default")
      (node (ref "U4") (pin "8") (pinfunction "DIO3_8") (pintype "bidirectional+no_connect"))
    )
    (net (code "64") (name "unconnected-(U4-DIO4-Pad10)") (class "Default")
      (node (ref "U4") (pin "10") (pinfunction "DIO4_10") (pintype "bidirectional+no_connect"))
    )
    (net (code "65") (name "unconnected-(U4-DIO5-Pad11)") (class "Default")
      (node (ref "U4") (pin "11") (pinfunction "DIO5_11") (pintype "bidirectional+no_connect"))
    )
    (net (code "66") (name "unconnected-(U5-CS-Pad6)") (class "Default")
      (node (ref "U5") (pin "6") (pinfunction "CS_6") (pintype "input+no_connect"))
    )
    (net (code "67") (name "unconnected-(U5-INT_RDY-Pad7)") (class "Default")
      (node (ref "U5") (pin "7") (pinfunction "INT_RDY_7") (pintype "output+no_connect"))
    )
    (net (code "68") (name "unconnected-(U5-SA0{slash}SDO-Pad5)") (class "Default")
      (node (ref "U5") (pin "5") (pinfunction "SA0/SDO_5") (pintype "bidirectional+no_connect"))
    )
    (net (code "69") (name "unconnected-(U8-N{slash}C-Pad3)") (class "Default")
      (node (ref "U8") (pin "3") (pinfunction "N/C_3") (pintype "passive+no_connect"))
    )
    (net (code "70") (name "unconnected-(U8-N{slash}C-Pad4)") (class "Default")
      (node (ref "U8") (pin "4") (pinfunction "N/C_4") (pintype "passive+no_connect"))
    )
  )
)
